# heater_test_1.net
KiCad netlist of a schematic drawn in EAGLE
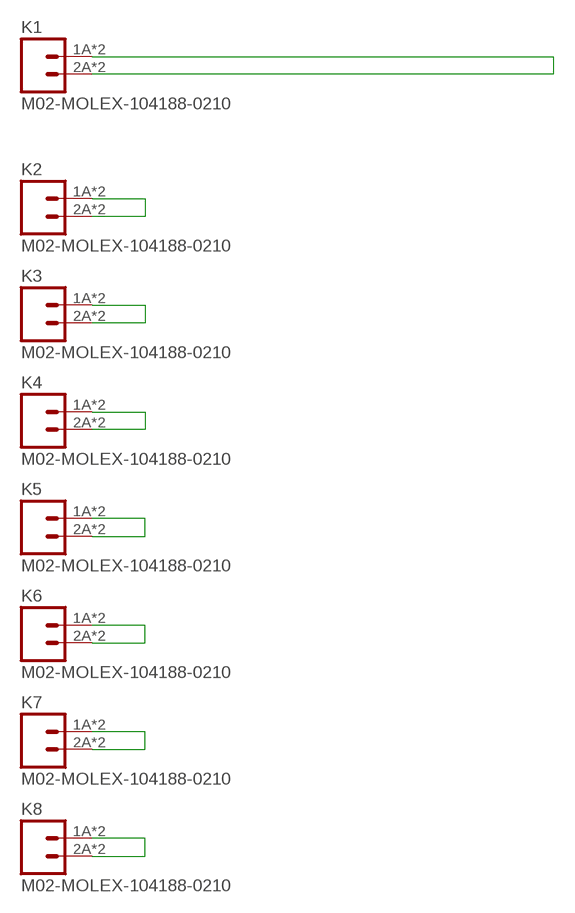
[diagram p0: schematic, sheet 1]

(export (version "E")
  (design (tool "Eeschema 10.0.6"))
  (components
    (comp (ref "K1")
      (value "M02-MOLEX-104188-0210")
      (footprint "eagle-import:LITE-TRAP-CONNECTOR-2")
      (libsource (lib "eagle-import") (part "M02-MOLEX-104188-0210"))
    )
    (comp (ref "K2")
      (value "M02-MOLEX-104188-0210")
      (footprint "eagle-import:LITE-TRAP-CONNECTOR-2")
      (libsource (lib "eagle-import") (part "M02-MOLEX-104188-0210"))
    )
    (comp (ref "K3")
      (value "M02-MOLEX-104188-0210")
      (footprint "eagle-import:LITE-TRAP-CONNECTOR-2")
      (libsource (lib "eagle-import") (part "M02-MOLEX-104188-0210"))
    )
    (comp (ref "K4")
      (value "M02-MOLEX-104188-0210")
      (footprint "eagle-import:LITE-TRAP-CONNECTOR-2")
      (libsource (lib "eagle-import") (part "M02-MOLEX-104188-0210"))
    )
    (comp (ref "K5")
      (value "M02-MOLEX-104188-0210")
      (footprint "eagle-import:LITE-TRAP-CONNECTOR-2")
      (libsource (lib "eagle-import") (part "M02-MOLEX-104188-0210"))
    )
    (comp (ref "K6")
      (value "M02-MOLEX-104188-0210")
      (footprint "eagle-import:LITE-TRAP-CONNECTOR-2")
      (libsource (lib "eagle-import") (part "M02-MOLEX-104188-0210"))
    )
    (comp (ref "K7")
      (value "M02-MOLEX-104188-0210")
      (footprint "eagle-import:LITE-TRAP-CONNECTOR-2")
      (libsource (lib "eagle-import") (part "M02-MOLEX-104188-0210"))
    )
    (comp (ref "K8")
      (value "M02-MOLEX-104188-0210")
      (footprint "eagle-import:LITE-TRAP-CONNECTOR-2")
      (libsource (lib "eagle-import") (part "M02-MOLEX-104188-0210"))
    )
  )
  (nets
    (net (code "1") (name "Net-(K1-1-Pad1A)") (class "Default")
      (node (ref "K1") (pin "1A") (pinfunction "1_1A") (pintype "passive"))
      (node (ref "K1") (pin "1B") (pinfunction "1_1B") (pintype "passive"))
      (node (ref "K1") (pin "2A") (pinfunction "2_2A") (pintype "passive"))
      (node (ref "K1") (pin "2B") (pinfunction "2_2B") (pintype "passive"))
    )
    (net (code "2") (name "Net-(K2-1-Pad1A)") (class "Default")
      (node (ref "K2") (pin "1A") (pinfunction "1_1A") (pintype "passive"))
      (node (ref "K2") (pin "1B") (pinfunction "1_1B") (pintype "passive"))
      (node (ref "K2") (pin "2A") (pinfunction "2_2A") (pintype "passive"))
      (node (ref "K2") (pin "2B") (pinfunction "2_2B") (pintype "passive"))
    )
    (net (code "3") (name "Net-(K3-1-Pad1A)") (class "Default")
      (node (ref "K3") (pin "1A") (pinfunction "1_1A") (pintype "passive"))
      (node (ref "K3") (pin "1B") (pinfunction "1_1B") (pintype "passive"))
      (node (ref "K3") (pin "2A") (pinfunction "2_2A") (pintype "passive"))
      (node (ref "K3") (pin "2B") (pinfunction "2_2B") (pintype "passive"))
    )
    (net (code "4") (name "Net-(K4-1-Pad1A)") (class "Default")
      (node (ref "K4") (pin "1A") (pinfunction "1_1A") (pintype "passive"))
      (node (ref "K4") (pin "1B") (pinfunction "1_1B") (pintype "passive"))
      (node (ref "K4") (pin "2A") (pinfunction "2_2A") (pintype "passive"))
      (node (ref "K4") (pin "2B") (pinfunction "2_2B") (pintype "passive"))
    )
    (net (code "5") (name "Net-(K5-1-Pad1A)") (class "Default")
      (node (ref "K5") (pin "1A") (pinfunction "1_1A") (pintype "passive"))
      (node (ref "K5") (pin "1B") (pinfunction "1_1B") (pintype "passive"))
      (node (ref "K5") (pin "2A") (pinfunction "2_2A") (pintype "passive"))
      (node (ref "K5") (pin "2B") (pinfunction "2_2B") (pintype "passive"))
    )
    (net (code "6") (name "Net-(K6-1-Pad1A)") (class "Default")
      (node (ref "K6") (pin "1A") (pinfunction "1_1A") (pintype "passive"))
      (node (ref "K6") (pin "1B") (pinfunction "1_1B") (pintype "passive"))
      (node (ref "K6") (pin "2A") (pinfunction "2_2A") (pintype "passive"))
      (node (ref "K6") (pin "2B") (pinfunction "2_2B") (pintype "passive"))
    )
    (net (code "7") (name "Net-(K7-1-Pad1A)") (class "Default")
      (node (ref "K7") (pin "1A") (pinfunction "1_1A") (pintype "passive"))
      (node (ref "K7") (pin "1B") (pinfunction "1_1B") (pintype "passive"))
      (node (ref "K7") (pin "2A") (pinfunction "2_2A") (pintype "passive"))
      (node (ref "K7") (pin "2B") (pinfunction "2_2B") (pintype "passive"))
    )
    (net (code "8") (name "Net-(K8-1-Pad1A)") (class "Default")
      (node (ref "K8") (pin "1A") (pinfunction "1_1A") (pintype "passive"))
      (node (ref "K8") (pin "1B") (pinfunction "1_1B") (pintype "passive"))
      (node (ref "K8") (pin "2A") (pinfunction "2_2A") (pintype "passive"))
      (node (ref "K8") (pin "2B") (pinfunction "2_2B") (pintype "passive"))
    )
  )
)
